# V1_0.net
KiCad netlist of a schematic drawn in Altium Designer
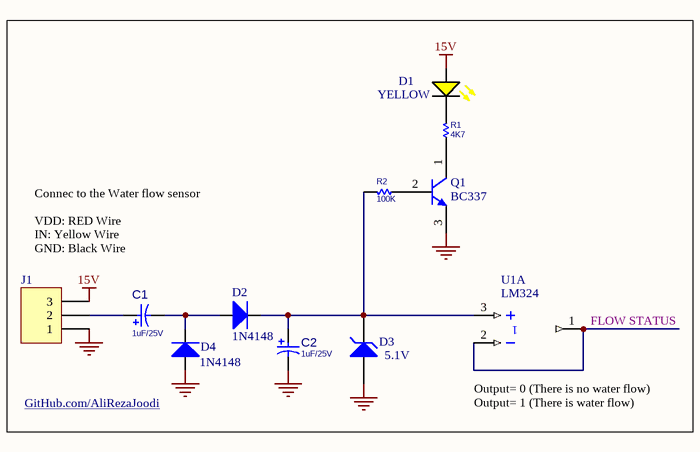
[diagram p0: V1.0.SchDoc]

(export (version "E")
  (design (tool "Eeschema 10.0.6"))
  (components
    (comp (ref "C1")
      (value "1uF/25V")
      (footprint "C_THD_EL_(P2.54-D6-H11)")
      (description "Capacitor, Electrolytic")
      (libsource (lib "Passive") (part "Capacitor_Electrolytic"))
    )
    (comp (ref "C2")
      (value "1uF/25V")
      (footprint "C_THD_EL_(P2.54-D6-H11)")
      (description "Capacitor, Electrolytic")
      (libsource (lib "Passive") (part "Capacitor_Electrolytic"))
    )
    (comp (ref "D1")
      (value "YELLOW")
      (footprint "LED_THD_5MM_YELLOW")
      (description "LED, Yellow")
      (fields (field (name "MANUFACTURER") "Generic Components") (field (name "PUBLISHER") "Altium Limited"))
      (libsource (lib "Display") (part "LED_YELLOW"))
    )
    (comp (ref "D2")
      (value "1N4148")
      (footprint "D_THD_AXIAL0.3_DO-35")
      (description "Default Diode")
      (fields (field (name "MANUFACTURER") "Generic Components") (field (name "PUBLISHER") "Altium Limited"))
      (libsource (lib "Miscellaneous Devices") (part "Diode"))
    )
    (comp (ref "D3")
      (value "5.1V")
      (footprint "D_THD_AXIAL0.3_DO-35")
      (description "Zener Diode")
      (fields (field (name "MANUFACTURER") "Generic Components") (field (name "PUBLISHER") "Altium Limited"))
      (libsource (lib "Miscellaneous Devices") (part "D Zener"))
    )
    (comp (ref "D4")
      (value "1N4148")
      (footprint "D_THD_AXIAL0.3_DO-35")
      (description "Default Diode")
      (fields (field (name "MANUFACTURER") "Generic Components") (field (name "PUBLISHER") "Altium Limited"))
      (libsource (lib "Miscellaneous Devices") (part "Diode"))
    )
    (comp (ref "J1")
      (value "J8")
      (footprint "Connector_Phoenix_3PIN_MSTB")
      (description "Header, 3-Pin")
      (fields (field (name "MANUFACTURER") "Generic Components") (field (name "PUBLISHER") "Altium Limited"))
      (libsource (lib "Miscellaneous Connectors") (part "Header 3"))
    )
    (comp (ref "Q1")
      (value "BC337")
      (footprint "TO92_3Pin_Form3")
      (description "Transistor, BJT, NPN")
      (libsource (lib "Passive") (part "Transistor_BJT_NPN"))
    )
    (comp (ref "R1")
      (value "4K7")
      (footprint "R_THD_AXIAL0.4(1/4W)")
      (description "Resistor,")
      (libsource (lib "Passive") (part "Resistor"))
    )
    (comp (ref "R2")
      (value "100K")
      (footprint "R_THD_AXIAL0.4(1/4W)")
      (description "Resistor,")
      (libsource (lib "Passive") (part "Resistor"))
    )
    (comp (ref "U1")
      (value "LM324")
      (footprint "DIP_14")
      (description "Quad Low-Power Operational Amplifier")
      (fields (field (name "PUBLISHER") "Altium Limited"))
      (libsource (lib "Other_Myself") (part "LM324"))
    )
  )
  (nets
    (net (code "1") (name "/FLOW STATUS") (class "Default")
      (node (ref "U1") (pin "1") (pinfunction "OUT_1") (pintype "output"))
      (node (ref "U1") (pin "2") (pinfunction "IN-_2") (pintype "input"))
    )
    (net (code "2") (name "15V") (class "Default")
      (node (ref "D1") (pin "1") (pinfunction "A_1") (pintype "passive"))
      (node (ref "J1") (pin "3") (pinfunction "3_3") (pintype "passive"))
    )
    (net (code "3") (name "GND") (class "Default")
      (node (ref "C2") (pin "2") (pinfunction "2_2") (pintype "passive"))
      (node (ref "D3") (pin "1") (pinfunction "A_1") (pintype "passive"))
      (node (ref "D4") (pin "1") (pinfunction "A_1") (pintype "passive"))
      (node (ref "J1") (pin "1") (pinfunction "1_1") (pintype "passive"))
      (node (ref "Q1") (pin "3") (pinfunction "E_3") (pintype "passive"))
    )
    (net (code "4") (name "Net-(C1-Pad1)") (class "Default")
      (node (ref "C1") (pin "1") (pinfunction "1_1") (pintype "passive"))
      (node (ref "J1") (pin "2") (pinfunction "2_2") (pintype "passive"))
    )
    (net (code "5") (name "Net-(D1-K)") (class "Default")
      (node (ref "D1") (pin "2") (pinfunction "K_2") (pintype "passive"))
      (node (ref "R1") (pin "1") (pinfunction "1_1") (pintype "passive"))
    )
    (net (code "6") (name "Net-(D2-A)") (class "Default")
      (node (ref "C1") (pin "2") (pinfunction "2_2") (pintype "passive"))
      (node (ref "D2") (pin "1") (pinfunction "A_1") (pintype "passive"))
      (node (ref "D4") (pin "2") (pinfunction "K_2") (pintype "passive"))
    )
    (net (code "7") (name "Net-(D2-K)") (class "Default")
      (node (ref "C2") (pin "1") (pinfunction "1_1") (pintype "passive"))
      (node (ref "D2") (pin "2") (pinfunction "K_2") (pintype "passive"))
      (node (ref "D3") (pin "2") (pinfunction "K_2") (pintype "passive"))
      (node (ref "R2") (pin "1") (pinfunction "1_1") (pintype "passive"))
      (node (ref "U1") (pin "3") (pinfunction "IN+_3") (pintype "input"))
    )
    (net (code "8") (name "Net-(Q1-B)") (class "Default")
      (node (ref "Q1") (pin "2") (pinfunction "B_2") (pintype "passive"))
      (node (ref "R2") (pin "2") (pinfunction "2_2") (pintype "passive"))
    )
    (net (code "9") (name "Net-(Q1-C)") (class "Default")
      (node (ref "Q1") (pin "1") (pinfunction "C_1") (pintype "passive"))
      (node (ref "R1") (pin "2") (pinfunction "2_2") (pintype "passive"))
    )
  )
)
